# 7Seg.net
KiCad netlist of a schematic drawn in Altium Designer
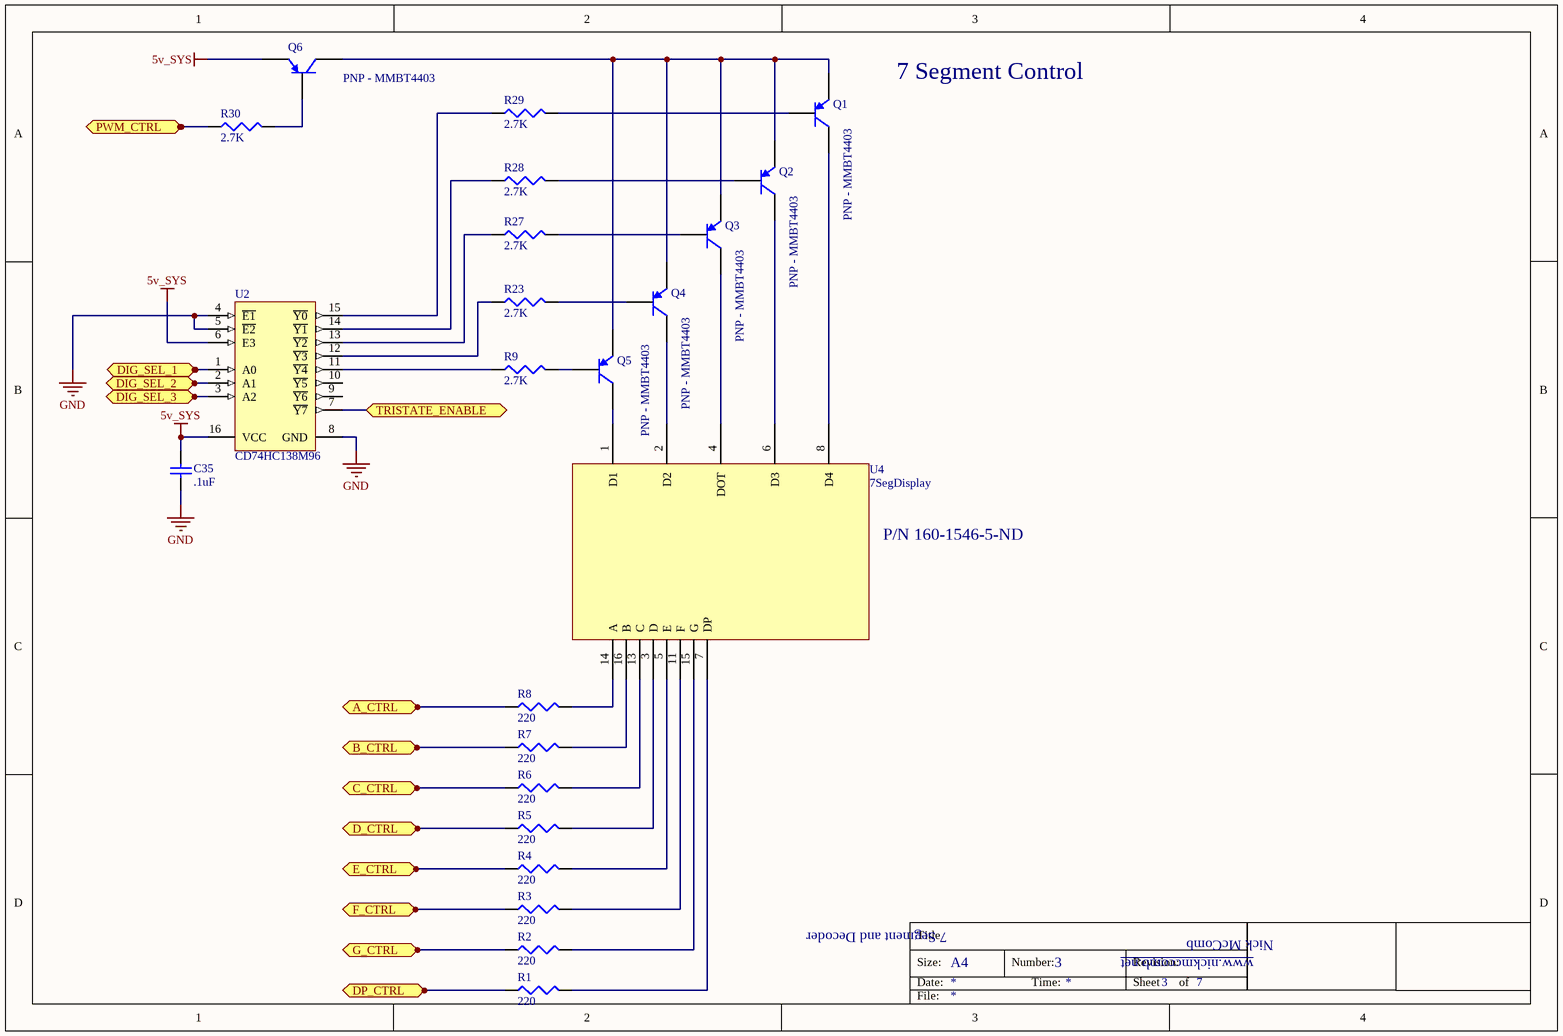
[diagram p0: 7Seg.SchDoc]

(export (version "E")
  (design (tool "Eeschema 10.0.6"))
  (components
    (comp (ref "C35")
      (value ".1uF")
      (footprint "C0805")
      (description "Capacitor")
      (fields (field (name "Comment") "0805 style, by default") (field (name "PUBLISHER") "Altium Limited"))
      (libsource (lib "lab2") (part "Cap"))
    )
    (comp (ref "Q1")
      (value "PNP - MMBT4403")
      (footprint "TO-92A - BJT")
      (description "PNP Bipolar Transistor")
      (libsource (lib "lab2") (part "PNP - MMBT4403"))
    )
    (comp (ref "Q2")
      (value "PNP - MMBT4403")
      (footprint "TO-92A - BJT")
      (description "PNP Bipolar Transistor")
      (libsource (lib "lab2") (part "PNP - MMBT4403"))
    )
    (comp (ref "Q3")
      (value "PNP - MMBT4403")
      (footprint "TO-92A - BJT")
      (description "PNP Bipolar Transistor")
      (libsource (lib "lab2") (part "PNP - MMBT4403"))
    )
    (comp (ref "Q4")
      (value "PNP - MMBT4403")
      (footprint "TO-92A - BJT")
      (description "PNP Bipolar Transistor")
      (libsource (lib "lab2") (part "PNP - MMBT4403"))
    )
    (comp (ref "Q5")
      (value "PNP - MMBT4403")
      (footprint "TO-92A - BJT")
      (description "PNP Bipolar Transistor")
      (libsource (lib "lab2") (part "PNP - MMBT4403"))
    )
    (comp (ref "Q6")
      (value "PNP - MMBT4403")
      (footprint "TO-92A - BJT")
      (description "PNP Bipolar Transistor")
      (libsource (lib "lab2") (part "PNP - MMBT4403"))
    )
    (comp (ref "R1")
      (value "220")
      (footprint "J1-0603")
      (description "Resistor")
      (fields (field (name "PUBLISHER") "Altium Limited"))
      (libsource (lib "lab2") (part "Res3"))
    )
    (comp (ref "R2")
      (value "220")
      (footprint "J1-0603")
      (description "Resistor")
      (fields (field (name "PUBLISHER") "Altium Limited"))
      (libsource (lib "lab2") (part "Res3"))
    )
    (comp (ref "R3")
      (value "220")
      (footprint "J1-0603")
      (description "Resistor")
      (fields (field (name "PUBLISHER") "Altium Limited"))
      (libsource (lib "lab2") (part "Res3"))
    )
    (comp (ref "R4")
      (value "220")
      (footprint "J1-0603")
      (description "Resistor")
      (fields (field (name "PUBLISHER") "Altium Limited"))
      (libsource (lib "lab2") (part "Res3"))
    )
    (comp (ref "R5")
      (value "220")
      (footprint "J1-0603")
      (description "Resistor")
      (fields (field (name "PUBLISHER") "Altium Limited"))
      (libsource (lib "lab2") (part "Res3"))
    )
    (comp (ref "R6")
      (value "220")
      (footprint "J1-0603")
      (description "Resistor")
      (fields (field (name "PUBLISHER") "Altium Limited"))
      (libsource (lib "lab2") (part "Res3"))
    )
    (comp (ref "R7")
      (value "220")
      (footprint "J1-0603")
      (description "Resistor")
      (fields (field (name "PUBLISHER") "Altium Limited"))
      (libsource (lib "lab2") (part "Res3"))
    )
    (comp (ref "R8")
      (value "220")
      (footprint "J1-0603")
      (description "Resistor")
      (fields (field (name "PUBLISHER") "Altium Limited"))
      (libsource (lib "lab2") (part "Res3"))
    )
    (comp (ref "R9")
      (value "2.7K")
      (footprint "J1-0603")
      (description "Resistor")
      (fields (field (name "PUBLISHER") "Altium Limited"))
      (libsource (lib "lab2") (part "Res3"))
    )
    (comp (ref "R23")
      (value "2.7K")
      (footprint "J1-0603")
      (description "Resistor")
      (fields (field (name "PUBLISHER") "Altium Limited"))
      (libsource (lib "lab2") (part "Res3"))
    )
    (comp (ref "R27")
      (value "2.7K")
      (footprint "J1-0603")
      (description "Resistor")
      (fields (field (name "PUBLISHER") "Altium Limited"))
      (libsource (lib "lab2") (part "Res3"))
    )
    (comp (ref "R28")
      (value "2.7K")
      (footprint "J1-0603")
      (description "Resistor")
      (fields (field (name "PUBLISHER") "Altium Limited"))
      (libsource (lib "lab2") (part "Res3"))
    )
    (comp (ref "R29")
      (value "2.7K")
      (footprint "J1-0603")
      (description "Resistor")
      (fields (field (name "PUBLISHER") "Altium Limited"))
      (libsource (lib "lab2") (part "Res3"))
    )
    (comp (ref "R30")
      (value "2.7K")
      (footprint "J1-0603")
      (description "Resistor")
      (fields (field (name "PUBLISHER") "Altium Limited"))
      (libsource (lib "lab2") (part "Res3"))
    )
    (comp (ref "U2")
      (value "CD74HC138M96")
      (footprint "D0016A_L")
      (fields
        (field (name "GENERIC PART NUMBER") "CD74HC138")
        (field (name "MANUFACTURER") "Texas Instruments")
      )
      (libsource (lib "Altium Content Vault") (part "TI-CDX4HCT138-16"))
    )
    (comp (ref "U4")
      (value "7SegDisplay")
      (footprint "LTC-4627JS")
      (libsource (lib "lab2") (part "7SegDisplay"))
    )
  )
  (nets
    (net (code "1") (name "/A_CTRL") (class "Default")
      (node (ref "R8") (pin "1") (pinfunction "1_1") (pintype "passive"))
    )
    (net (code "2") (name "/B_CTRL") (class "Default")
      (node (ref "R7") (pin "1") (pinfunction "1_1") (pintype "passive"))
    )
    (net (code "3") (name "/C_CTRL") (class "Default")
      (node (ref "R6") (pin "1") (pinfunction "1_1") (pintype "passive"))
    )
    (net (code "4") (name "/DIG_SEL_1") (class "Default")
      (node (ref "U2") (pin "1") (pinfunction "A0_1") (pintype "input"))
    )
    (net (code "5") (name "/DIG_SEL_2") (class "Default")
      (node (ref "U2") (pin "2") (pinfunction "A1_2") (pintype "input"))
    )
    (net (code "6") (name "/DIG_SEL_3") (class "Default")
      (node (ref "U2") (pin "3") (pinfunction "A2_3") (pintype "input"))
    )
    (net (code "7") (name "/DP_CTRL") (class "Default")
      (node (ref "R1") (pin "1") (pinfunction "1_1") (pintype "passive"))
    )
    (net (code "8") (name "/D_CTRL") (class "Default")
      (node (ref "R5") (pin "1") (pinfunction "1_1") (pintype "passive"))
    )
    (net (code "9") (name "/E_CTRL") (class "Default")
      (node (ref "R4") (pin "1") (pinfunction "1_1") (pintype "passive"))
    )
    (net (code "10") (name "/F_CTRL") (class "Default")
      (node (ref "R3") (pin "1") (pinfunction "1_1") (pintype "passive"))
    )
    (net (code "11") (name "/G_CTRL") (class "Default")
      (node (ref "R2") (pin "1") (pinfunction "1_1") (pintype "passive"))
    )
    (net (code "12") (name "/PWM_CTRL") (class "Default")
      (node (ref "R30") (pin "1") (pinfunction "1_1") (pintype "passive"))
    )
    (net (code "13") (name "/TRISTATE_ENABLE") (class "Default")
      (node (ref "U2") (pin "7") (pinfunction "~{Y7}_7") (pintype "output"))
    )
    (net (code "14") (name "5v_SYS") (class "Default")
      (node (ref "C35") (pin "2") (pinfunction "2_2") (pintype "passive"))
      (node (ref "Q6") (pin "3") (pinfunction "E_3") (pintype "passive"))
      (node (ref "U2") (pin "16") (pinfunction "VCC_16") (pintype "power_in"))
      (node (ref "U2") (pin "6") (pinfunction "E3_6") (pintype "input"))
    )
    (net (code "15") (name "GND") (class "Default")
      (node (ref "C35") (pin "1") (pinfunction "1_1") (pintype "passive"))
      (node (ref "U2") (pin "4") (pinfunction "~{E1}_4") (pintype "input"))
      (node (ref "U2") (pin "5") (pinfunction "~{E2}_5") (pintype "input"))
      (node (ref "U2") (pin "8") (pinfunction "GND_8") (pintype "power_in"))
    )
    (net (code "16") (name "Net-(Q1-B)") (class "Default")
      (node (ref "Q1") (pin "2") (pinfunction "B_2") (pintype "passive"))
      (node (ref "R29") (pin "2") (pinfunction "2_2") (pintype "passive"))
    )
    (net (code "17") (name "Net-(Q1-C)") (class "Default")
      (node (ref "Q1") (pin "1") (pinfunction "C_1") (pintype "passive"))
      (node (ref "U4") (pin "8") (pinfunction "D4_8") (pintype "passive"))
    )
    (net (code "18") (name "Net-(Q1-E)") (class "Default")
      (node (ref "Q1") (pin "3") (pinfunction "E_3") (pintype "passive"))
      (node (ref "Q2") (pin "3") (pinfunction "E_3") (pintype "passive"))
      (node (ref "Q3") (pin "3") (pinfunction "E_3") (pintype "passive"))
      (node (ref "Q4") (pin "3") (pinfunction "E_3") (pintype "passive"))
      (node (ref "Q5") (pin "3") (pinfunction "E_3") (pintype "passive"))
      (node (ref "Q6") (pin "1") (pinfunction "C_1") (pintype "passive"))
    )
    (net (code "19") (name "Net-(Q2-B)") (class "Default")
      (node (ref "Q2") (pin "2") (pinfunction "B_2") (pintype "passive"))
      (node (ref "R28") (pin "2") (pinfunction "2_2") (pintype "passive"))
    )
    (net (code "20") (name "Net-(Q2-C)") (class "Default")
      (node (ref "Q2") (pin "1") (pinfunction "C_1") (pintype "passive"))
      (node (ref "U4") (pin "6") (pinfunction "D3_6") (pintype "passive"))
    )
    (net (code "21") (name "Net-(Q3-B)") (class "Default")
      (node (ref "Q3") (pin "2") (pinfunction "B_2") (pintype "passive"))
      (node (ref "R27") (pin "2") (pinfunction "2_2") (pintype "passive"))
    )
    (net (code "22") (name "Net-(Q3-C)") (class "Default")
      (node (ref "Q3") (pin "1") (pinfunction "C_1") (pintype "passive"))
      (node (ref "U4") (pin "4") (pinfunction "DOT_4") (pintype "passive"))
    )
    (net (code "23") (name "Net-(Q4-B)") (class "Default")
      (node (ref "Q4") (pin "2") (pinfunction "B_2") (pintype "passive"))
      (node (ref "R23") (pin "2") (pinfunction "2_2") (pintype "passive"))
    )
    (net (code "24") (name "Net-(Q4-C)") (class "Default")
      (node (ref "Q4") (pin "1") (pinfunction "C_1") (pintype "passive"))
      (node (ref "U4") (pin "2") (pinfunction "D2_2") (pintype "passive"))
    )
    (net (code "25") (name "Net-(Q5-B)") (class "Default")
      (node (ref "Q5") (pin "2") (pinfunction "B_2") (pintype "passive"))
      (node (ref "R9") (pin "2") (pinfunction "2_2") (pintype "passive"))
    )
    (net (code "26") (name "Net-(Q5-C)") (class "Default")
      (node (ref "Q5") (pin "1") (pinfunction "C_1") (pintype "passive"))
      (node (ref "U4") (pin "1") (pinfunction "D1_1") (pintype "passive"))
    )
    (net (code "27") (name "Net-(Q6-B)") (class "Default")
      (node (ref "Q6") (pin "2") (pinfunction "B_2") (pintype "passive"))
      (node (ref "R30") (pin "2") (pinfunction "2_2") (pintype "passive"))
    )
    (net (code "28") (name "Net-(U2-~{Y0})") (class "Default")
      (node (ref "R29") (pin "1") (pinfunction "1_1") (pintype "passive"))
      (node (ref "U2") (pin "15") (pinfunction "~{Y0}_15") (pintype "output"))
    )
    (net (code "29") (name "Net-(U2-~{Y1})") (class "Default")
      (node (ref "R28") (pin "1") (pinfunction "1_1") (pintype "passive"))
      (node (ref "U2") (pin "14") (pinfunction "~{Y1}_14") (pintype "output"))
    )
    (net (code "30") (name "Net-(U2-~{Y2})") (class "Default")
      (node (ref "R27") (pin "1") (pinfunction "1_1") (pintype "passive"))
      (node (ref "U2") (pin "13") (pinfunction "~{Y2}_13") (pintype "output"))
    )
    (net (code "31") (name "Net-(U2-~{Y3})") (class "Default")
      (node (ref "R23") (pin "1") (pinfunction "1_1") (pintype "passive"))
      (node (ref "U2") (pin "12") (pinfunction "~{Y3}_12") (pintype "output"))
    )
    (net (code "32") (name "Net-(U2-~{Y4})") (class "Default")
      (node (ref "R9") (pin "1") (pinfunction "1_1") (pintype "passive"))
      (node (ref "U2") (pin "11") (pinfunction "~{Y4}_11") (pintype "output"))
    )
    (net (code "33") (name "Net-(U4-A)") (class "Default")
      (node (ref "R8") (pin "2") (pinfunction "2_2") (pintype "passive"))
      (node (ref "U4") (pin "14") (pinfunction "A_14") (pintype "passive"))
    )
    (net (code "34") (name "Net-(U4-B)") (class "Default")
      (node (ref "R7") (pin "2") (pinfunction "2_2") (pintype "passive"))
      (node (ref "U4") (pin "16") (pinfunction "B_16") (pintype "passive"))
    )
    (net (code "35") (name "Net-(U4-C)") (class "Default")
      (node (ref "R6") (pin "2") (pinfunction "2_2") (pintype "passive"))
      (node (ref "U4") (pin "13") (pinfunction "C_13") (pintype "passive"))
    )
    (net (code "36") (name "Net-(U4-D)") (class "Default")
      (node (ref "R5") (pin "2") (pinfunction "2_2") (pintype "passive"))
      (node (ref "U4") (pin "3") (pinfunction "D_3") (pintype "passive"))
    )
    (net (code "37") (name "Net-(U4-DP)") (class "Default")
      (node (ref "R1") (pin "2") (pinfunction "2_2") (pintype "passive"))
      (node (ref "U4") (pin "7") (pinfunction "DP_7") (pintype "passive"))
    )
    (net (code "38") (name "Net-(U4-E)") (class "Default")
      (node (ref "R4") (pin "2") (pinfunction "2_2") (pintype "passive"))
      (node (ref "U4") (pin "5") (pinfunction "E_5") (pintype "passive"))
    )
    (net (code "39") (name "Net-(U4-F)") (class "Default")
      (node (ref "R3") (pin "2") (pinfunction "2_2") (pintype "passive"))
      (node (ref "U4") (pin "11") (pinfunction "F_11") (pintype "passive"))
    )
    (net (code "40") (name "Net-(U4-G)") (class "Default")
      (node (ref "R2") (pin "2") (pinfunction "2_2") (pintype "passive"))
      (node (ref "U4") (pin "15") (pinfunction "G_15") (pintype "passive"))
    )
    (net (code "41") (name "unconnected-(U2-~{Y5}-Pad10)") (class "Default")
      (node (ref "U2") (pin "10") (pinfunction "~{Y5}_10") (pintype "output"))
    )
    (net (code "42") (name "unconnected-(U2-~{Y6}-Pad9)") (class "Default")
      (node (ref "U2") (pin "9") (pinfunction "~{Y6}_9") (pintype "output"))
    )
  )
)
